# ds18b20_schematic_phase_3.net
KiCad netlist of a schematic drawn in EAGLE
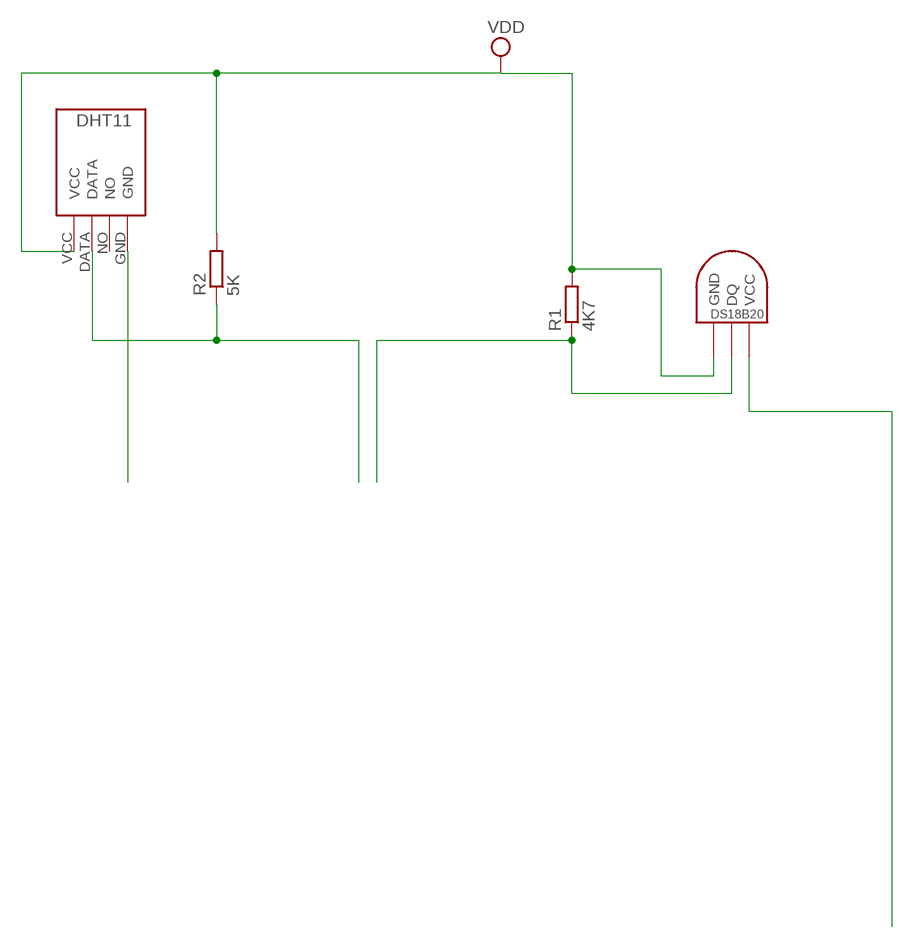
[diagram p0: schematic, sheet 1]

(export (version "E")
  (design (tool "Eeschema 10.0.6"))
  (components
    (comp (ref "R1")
      (value "4K7")
      (footprint "eagle-import:0204_7")
      (libsource (lib "eagle-import") (part "R-EU_0204/7"))
    )
    (comp (ref "R2")
      (value "5K")
      (footprint "eagle-import:0204_7")
      (libsource (lib "eagle-import") (part "R-EU_0204/7"))
    )
    (comp (ref "U$1")
      (value "DS1820TO92")
      (footprint "eagle-import:DS1820")
      (libsource (lib "eagle-import") (part "DS1820TO92"))
    )
    (comp (ref "U$2")
      (value "DHT11-PION.")
      (footprint "eagle-import:DHT11-PION.")
      (libsource (lib "eagle-import") (part "DHT11-PION."))
    )
  )
  (nets
    (net (code "1") (name "Net-(R1-Pad1)") (class "Default")
      (node (ref "R1") (pin "1") (pinfunction "1_1") (pintype "passive"))
      (node (ref "U$1") (pin "DQ") (pinfunction "DQ_DQ") (pintype "bidirectional"))
    )
    (net (code "2") (name "Net-(R2-Pad1)") (class "Default")
      (node (ref "R2") (pin "1") (pinfunction "1_1") (pintype "passive"))
      (node (ref "U$2") (pin "DATA") (pinfunction "DATA_DATA") (pintype "bidirectional"))
    )
    (net (code "3") (name "VDD") (class "Default")
      (node (ref "R1") (pin "2") (pinfunction "2_2") (pintype "passive"))
      (node (ref "R2") (pin "2") (pinfunction "2_2") (pintype "passive"))
      (node (ref "U$1") (pin "GND") (pinfunction "GND_GND") (pintype "power_in"))
      (node (ref "U$2") (pin "VCC") (pinfunction "VCC_VCC") (pintype "bidirectional"))
    )
    (net (code "4") (name "unconnected-(U$1-VCC-PadVDD)") (class "Default")
      (node (ref "U$1") (pin "VDD") (pinfunction "VCC_VDD") (pintype "power_in"))
    )
    (net (code "5") (name "unconnected-(U$2-PadGND)") (class "Default")
      (node (ref "U$2") (pin "GND") (pinfunction "GND_GND") (pintype "bidirectional"))
    )
    (net (code "6") (name "unconnected-(U$2-PadNO)") (class "Default")
      (node (ref "U$2") (pin "NO") (pinfunction "NO_NO") (pintype "bidirectional"))
    )
  )
)
